# BatteryTestBoard_V1.net
KiCad netlist of a schematic drawn in EAGLE
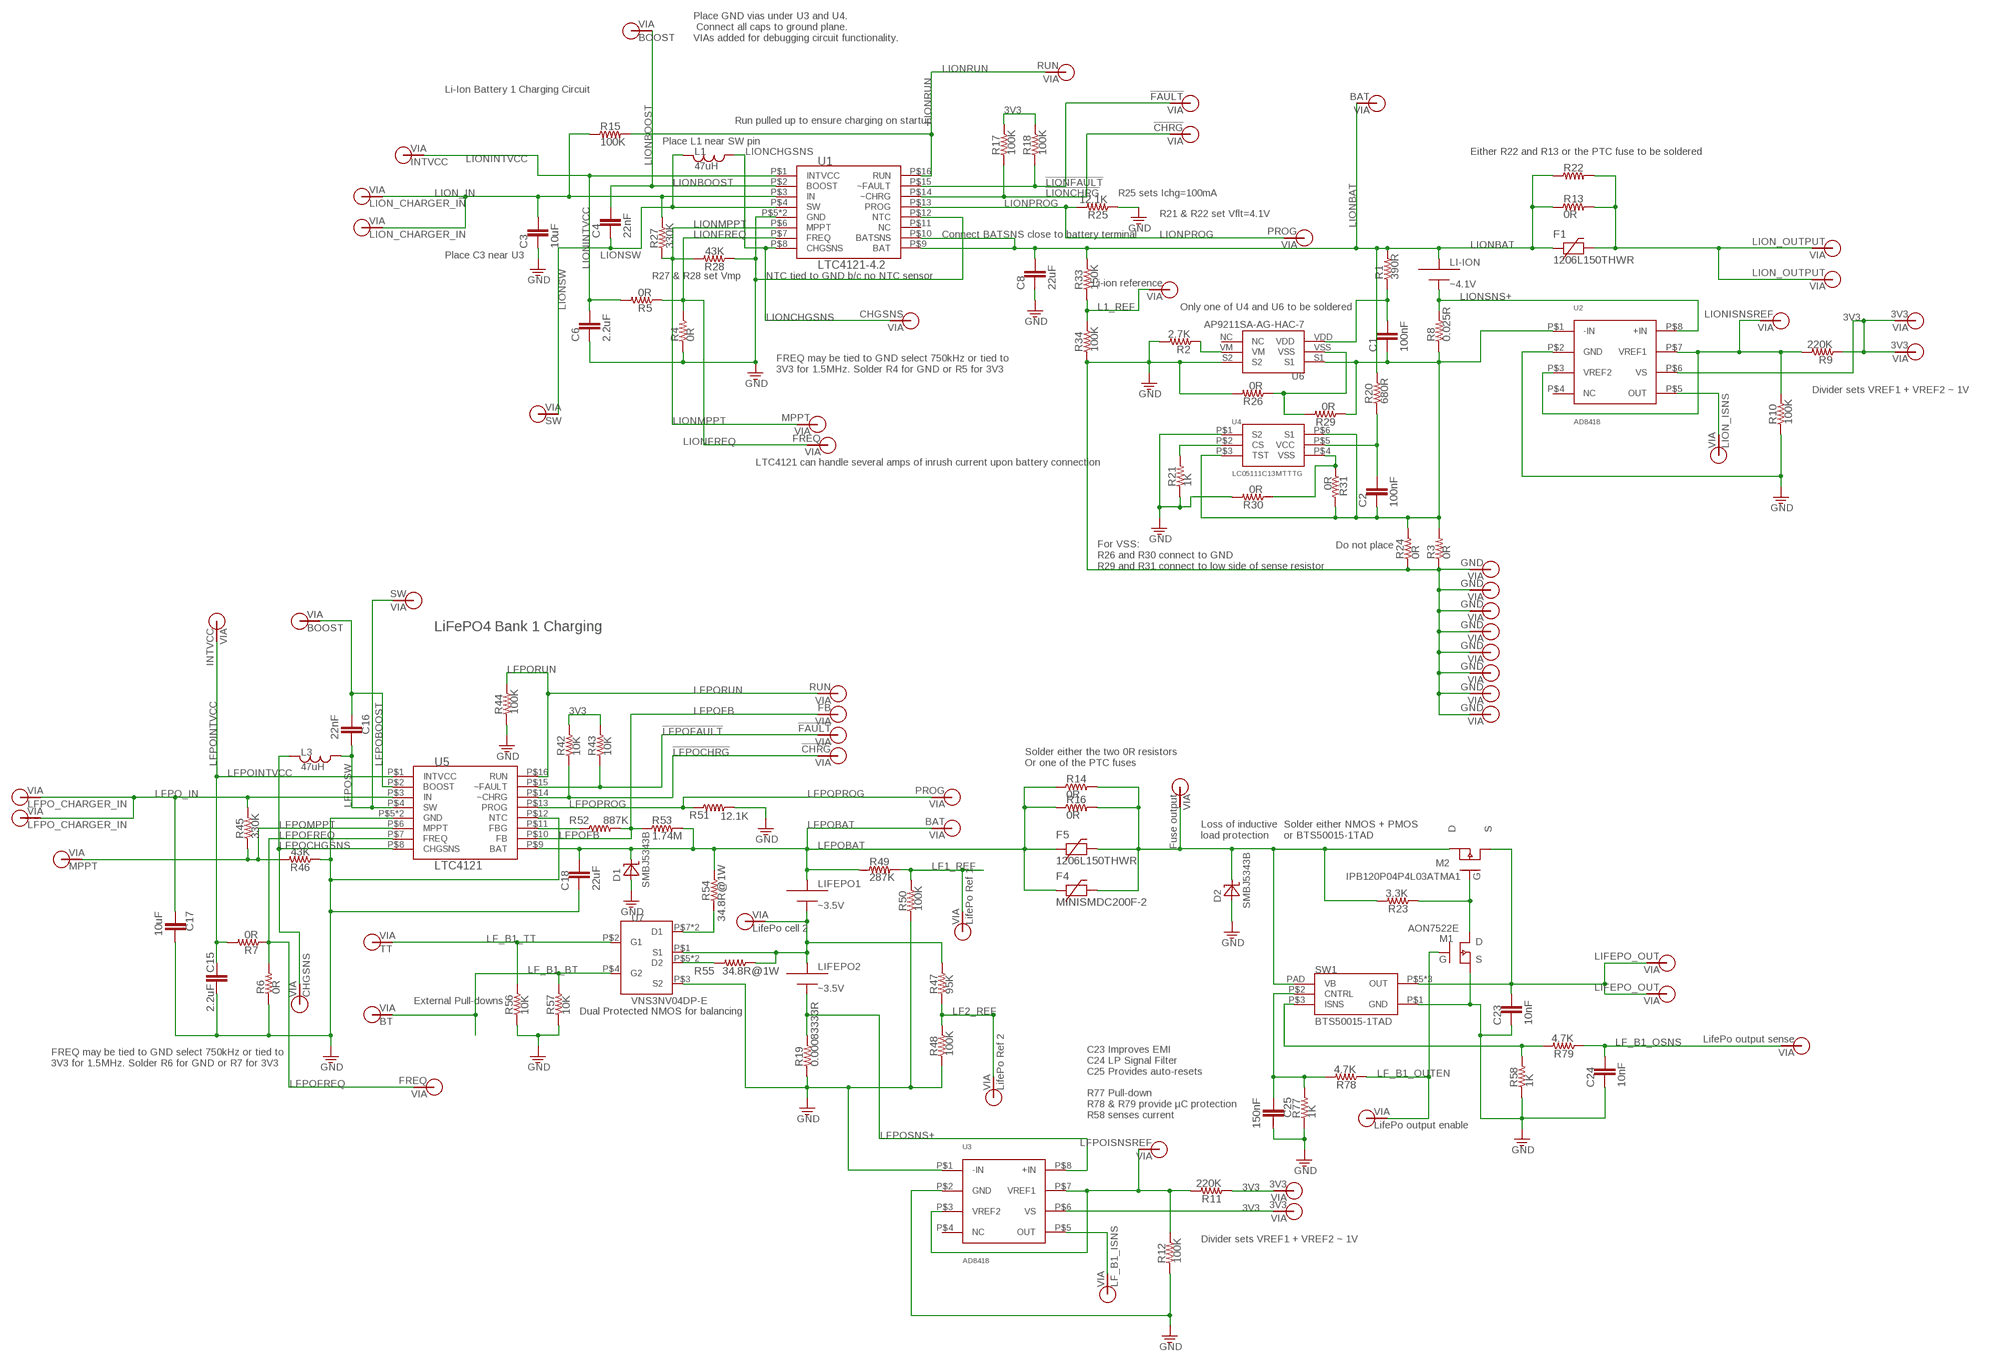
[diagram p0: schematic, sheet 1]

(export (version "E")
  (design (tool "Eeschema 10.0.6"))
  (components
    (comp (ref "C1")
      (value "100nF")
      (footprint "eagle-import:0805")
      (libsource (lib "eagle-import") (part "CAP0805"))
    )
    (comp (ref "C2")
      (value "100nF")
      (footprint "eagle-import:0805")
      (libsource (lib "eagle-import") (part "CAP0805"))
    )
    (comp (ref "C3")
      (value "10uF")
      (footprint "eagle-import:0805")
      (libsource (lib "eagle-import") (part "CAP0805"))
    )
    (comp (ref "C4")
      (value "22nF")
      (footprint "eagle-import:0805")
      (libsource (lib "eagle-import") (part "CAP0805"))
    )
    (comp (ref "C6")
      (value "2.2uF")
      (footprint "eagle-import:0805")
      (libsource (lib "eagle-import") (part "CAP0805"))
    )
    (comp (ref "C8")
      (value "22uF")
      (footprint "eagle-import:0805")
      (libsource (lib "eagle-import") (part "CAP0805"))
    )
    (comp (ref "C15")
      (value "2.2uF")
      (footprint "eagle-import:0805")
      (libsource (lib "eagle-import") (part "CAP0805"))
    )
    (comp (ref "C16")
      (value "22nF")
      (footprint "eagle-import:0805")
      (libsource (lib "eagle-import") (part "CAP0805"))
    )
    (comp (ref "C17")
      (value "10uF")
      (footprint "eagle-import:0805")
      (libsource (lib "eagle-import") (part "CAP0805"))
    )
    (comp (ref "C18")
      (value "22uF")
      (footprint "eagle-import:0805")
      (libsource (lib "eagle-import") (part "CAP0805"))
    )
    (comp (ref "C23")
      (value "10nF")
      (footprint "eagle-import:0805")
      (libsource (lib "eagle-import") (part "CAP0805"))
    )
    (comp (ref "C24")
      (value "10nF")
      (footprint "eagle-import:0805")
      (libsource (lib "eagle-import") (part "CAP0805"))
    )
    (comp (ref "C25")
      (value "150nF")
      (footprint "eagle-import:0805")
      (libsource (lib "eagle-import") (part "CAP0805"))
    )
    (comp (ref "D1")
      (value "SMBJ5343B")
      (footprint "eagle-import:DO214AA")
      (libsource (lib "eagle-import") (part "SMBJ5343B"))
    )
    (comp (ref "D2")
      (value "SMBJ5343B")
      (footprint "eagle-import:DO214AA")
      (libsource (lib "eagle-import") (part "SMBJ5343B"))
    )
    (comp (ref "F1")
      (value "1206L150THWR")
      (footprint "eagle-import:1206")
      (libsource (lib "eagle-import") (part "1206L150THWR"))
    )
    (comp (ref "F4")
      (value "MINISMDC200F-2")
      (footprint "eagle-import:1812")
      (libsource (lib "eagle-import") (part "MINISMDC200F-2"))
    )
    (comp (ref "F5")
      (value "1206L150THWR")
      (footprint "eagle-import:1206")
      (libsource (lib "eagle-import") (part "1206L150THWR"))
    )
    (comp (ref "L1")
      (value "47uH")
      (footprint "eagle-import:1812")
      (libsource (lib "eagle-import") (part "IND1812"))
    )
    (comp (ref "L3")
      (value "47uH")
      (footprint "eagle-import:1812")
      (libsource (lib "eagle-import") (part "IND1812"))
    )
    (comp (ref "LI-ION")
      (value "~4.1V")
      (footprint "eagle-import:EQUISAT-BATTERY-VA")
      (libsource (lib "eagle-import") (part "LI-ION"))
    )
    (comp (ref "LIFEPO1")
      (value "~3.5V")
      (footprint "eagle-import:EQUISAT-BATTERY-VA")
      (libsource (lib "eagle-import") (part "LIFEPO4VA"))
    )
    (comp (ref "LIFEPO2")
      (value "~3.5V")
      (footprint "eagle-import:EQUISAT-BATTERY-VA")
      (libsource (lib "eagle-import") (part "LIFEPO4VA"))
    )
    (comp (ref "M1")
      (value "AON7522E")
      (footprint "eagle-import:DFN-3X3-8")
      (libsource (lib "eagle-import") (part "AON7522E"))
    )
    (comp (ref "M2")
      (value "IPB120P04P4L03ATMA1")
      (footprint "eagle-import:TO263")
      (libsource (lib "eagle-import") (part "IPB120P04P4L03ATMA1"))
    )
    (comp (ref "R1")
      (value "390R")
      (footprint "eagle-import:0805")
      (libsource (lib "eagle-import") (part "RES0805"))
    )
    (comp (ref "R2")
      (value "2.7K")
      (footprint "eagle-import:0805")
      (libsource (lib "eagle-import") (part "RES0805"))
    )
    (comp (ref "R3")
      (value "0R")
      (footprint "eagle-import:1210")
      (libsource (lib "eagle-import") (part "RES1210"))
    )
    (comp (ref "R4")
      (value "0R")
      (footprint "eagle-import:0805")
      (libsource (lib "eagle-import") (part "RES0805"))
    )
    (comp (ref "R5")
      (value "0R")
      (footprint "eagle-import:0805")
      (libsource (lib "eagle-import") (part "RES0805"))
    )
    (comp (ref "R6")
      (value "0R")
      (footprint "eagle-import:0805")
      (libsource (lib "eagle-import") (part "RES0805"))
    )
    (comp (ref "R7")
      (value "0R")
      (footprint "eagle-import:0805")
      (libsource (lib "eagle-import") (part "RES0805"))
    )
    (comp (ref "R8")
      (value "0.025R")
      (footprint "eagle-import:1210")
      (libsource (lib "eagle-import") (part "RES1210"))
    )
    (comp (ref "R9")
      (value "220K")
      (footprint "eagle-import:0805")
      (libsource (lib "eagle-import") (part "RES0805"))
    )
    (comp (ref "R10")
      (value "100K")
      (footprint "eagle-import:0805")
      (libsource (lib "eagle-import") (part "RES0805"))
    )
    (comp (ref "R11")
      (value "220K")
      (footprint "eagle-import:0805")
      (libsource (lib "eagle-import") (part "RES0805"))
    )
    (comp (ref "R12")
      (value "100K")
      (footprint "eagle-import:0805")
      (libsource (lib "eagle-import") (part "RES0805"))
    )
    (comp (ref "R13")
      (value "0R")
      (footprint "eagle-import:1210")
      (libsource (lib "eagle-import") (part "RES1210"))
    )
    (comp (ref "R14")
      (value "0R")
      (footprint "eagle-import:1210")
      (libsource (lib "eagle-import") (part "RES1210"))
    )
    (comp (ref "R15")
      (value "100K")
      (footprint "eagle-import:0805")
      (libsource (lib "eagle-import") (part "RES0805"))
    )
    (comp (ref "R16")
      (value "0R")
      (footprint "eagle-import:1210")
      (libsource (lib "eagle-import") (part "RES1210"))
    )
    (comp (ref "R17")
      (value "100K")
      (footprint "eagle-import:0805")
      (libsource (lib "eagle-import") (part "RES0805"))
    )
    (comp (ref "R18")
      (value "100K")
      (footprint "eagle-import:0805")
      (libsource (lib "eagle-import") (part "RES0805"))
    )
    (comp (ref "R19")
      (value "0.00083333R")
      (footprint "eagle-import:1210")
      (libsource (lib "eagle-import") (part "RES1210"))
    )
    (comp (ref "R20")
      (value "680R")
      (footprint "eagle-import:0805")
      (libsource (lib "eagle-import") (part "RES0805"))
    )
    (comp (ref "R21")
      (value "1K")
      (footprint "eagle-import:0805")
      (libsource (lib "eagle-import") (part "RES0805"))
    )
    (comp (ref "R22")
      (value "0R")
      (footprint "eagle-import:1210")
      (libsource (lib "eagle-import") (part "RES1210"))
    )
    (comp (ref "R23")
      (value "3.3K")
      (footprint "eagle-import:0805")
      (libsource (lib "eagle-import") (part "RES0805"))
    )
    (comp (ref "R24")
      (value "0R")
      (footprint "eagle-import:1210")
      (libsource (lib "eagle-import") (part "RES1210"))
    )
    (comp (ref "R25")
      (value "12.1K")
      (footprint "eagle-import:0805")
      (libsource (lib "eagle-import") (part "RES0805"))
    )
    (comp (ref "R26")
      (value "0R")
      (footprint "eagle-import:0805")
      (libsource (lib "eagle-import") (part "RES0805"))
    )
    (comp (ref "R27")
      (value "330K")
      (footprint "eagle-import:0805")
      (libsource (lib "eagle-import") (part "RES0805"))
    )
    (comp (ref "R28")
      (value "43K")
      (footprint "eagle-import:0805")
      (libsource (lib "eagle-import") (part "RES0805"))
    )
    (comp (ref "R29")
      (value "0R")
      (footprint "eagle-import:0805")
      (libsource (lib "eagle-import") (part "RES0805"))
    )
    (comp (ref "R30")
      (value "0R")
      (footprint "eagle-import:0805")
      (libsource (lib "eagle-import") (part "RES0805"))
    )
    (comp (ref "R31")
      (value "0R")
      (footprint "eagle-import:0805")
      (libsource (lib "eagle-import") (part "RES0805"))
    )
    (comp (ref "R33")
      (value "150K")
      (footprint "eagle-import:0805")
      (libsource (lib "eagle-import") (part "RES0805"))
    )
    (comp (ref "R34")
      (value "100K")
      (footprint "eagle-import:0805")
      (libsource (lib "eagle-import") (part "RES0805"))
    )
    (comp (ref "R42")
      (value "10K")
      (footprint "eagle-import:0805")
      (libsource (lib "eagle-import") (part "RES0805"))
    )
    (comp (ref "R43")
      (value "10K")
      (footprint "eagle-import:0805")
      (libsource (lib "eagle-import") (part "RES0805"))
    )
    (comp (ref "R44")
      (value "100K")
      (footprint "eagle-import:0805")
      (libsource (lib "eagle-import") (part "RES0805"))
    )
    (comp (ref "R45")
      (value "330K")
      (footprint "eagle-import:0805")
      (libsource (lib "eagle-import") (part "RES0805"))
    )
    (comp (ref "R46")
      (value "43K")
      (footprint "eagle-import:0805")
      (libsource (lib "eagle-import") (part "RES0805"))
    )
    (comp (ref "R47")
      (value "95K")
      (footprint "eagle-import:0805")
      (libsource (lib "eagle-import") (part "RES0805"))
    )
    (comp (ref "R48")
      (value "100K")
      (footprint "eagle-import:0805")
      (libsource (lib "eagle-import") (part "RES0805"))
    )
    (comp (ref "R49")
      (value "287K")
      (footprint "eagle-import:0805")
      (libsource (lib "eagle-import") (part "RES0805"))
    )
    (comp (ref "R50")
      (value "100K")
      (footprint "eagle-import:0805")
      (libsource (lib "eagle-import") (part "RES0805"))
    )
    (comp (ref "R51")
      (value "12.1K")
      (footprint "eagle-import:0805")
      (libsource (lib "eagle-import") (part "RES0805"))
    )
    (comp (ref "R52")
      (value "887K")
      (footprint "eagle-import:0805")
      (libsource (lib "eagle-import") (part "RES0805"))
    )
    (comp (ref "R53")
      (value "1.74M")
      (footprint "eagle-import:0805")
      (libsource (lib "eagle-import") (part "RES0805"))
    )
    (comp (ref "R54")
      (value "34.8R@1W")
      (footprint "eagle-import:1210")
      (libsource (lib "eagle-import") (part "RES1210"))
    )
    (comp (ref "R55")
      (value "34.8R@1W")
      (footprint "eagle-import:1210")
      (libsource (lib "eagle-import") (part "RES1210"))
    )
    (comp (ref "R56")
      (value "10K")
      (footprint "eagle-import:0805")
      (libsource (lib "eagle-import") (part "RES0805"))
    )
    (comp (ref "R57")
      (value "10K")
      (footprint "eagle-import:0805")
      (libsource (lib "eagle-import") (part "RES0805"))
    )
    (comp (ref "R58")
      (value "1K")
      (footprint "eagle-import:0805")
      (libsource (lib "eagle-import") (part "RES0805"))
    )
    (comp (ref "R77")
      (value "1K")
      (footprint "eagle-import:0805")
      (libsource (lib "eagle-import") (part "RES0805"))
    )
    (comp (ref "R78")
      (value "4.7K")
      (footprint "eagle-import:0805")
      (libsource (lib "eagle-import") (part "RES0805"))
    )
    (comp (ref "R79")
      (value "4.7K")
      (footprint "eagle-import:0805")
      (libsource (lib "eagle-import") (part "RES0805"))
    )
    (comp (ref "SW1")
      (value "BTS50015-1TAD")
      (footprint "eagle-import:TO-263-7-8")
      (libsource (lib "eagle-import") (part "BTS50015-1TAD"))
    )
    (comp (ref "U1")
      (value "LTC4121-4.2")
      (footprint "eagle-import:QFN-16-PAD")
      (libsource (lib "eagle-import") (part "LTC4121-4.2"))
    )
    (comp (ref "U2")
      (value "AD8418")
      (footprint "eagle-import:MSOP-8")
      (libsource (lib "eagle-import") (part "AD8418"))
    )
    (comp (ref "U3")
      (value "AD8418")
      (footprint "eagle-import:MSOP-8")
      (libsource (lib "eagle-import") (part "AD8418"))
    )
    (comp (ref "U4")
      (value "LC05111C13MTTTG")
      (footprint "eagle-import:WDFN6")
      (libsource (lib "eagle-import") (part "LC05111C13MTTTG"))
    )
    (comp (ref "U5")
      (value "LTC4121")
      (footprint "eagle-import:QFN-16-PAD")
      (libsource (lib "eagle-import") (part "LTC4121"))
    )
    (comp (ref "U6")
      (value "AP9211SA-AG-HAC-7")
      (footprint "eagle-import:U-DFN2030-6")
      (libsource (lib "eagle-import") (part "AP9211SA-AG-HAC-7"))
    )
    (comp (ref "U7")
      (value "VNS3NV04DP-E")
      (footprint "eagle-import:SO-8")
      (libsource (lib "eagle-import") (part "VNS3NV04DP-E"))
    )
    (comp (ref "V1")
      (value "LION_OUTPUT")
      (footprint "eagle-import:VIA-120MIL")
      (libsource (lib "eagle-import") (part "VIA-120MIL"))
    )
    (comp (ref "V2")
      (value "Fuse output")
      (footprint "eagle-import:VIA-60MIL-SQ")
      (libsource (lib "eagle-import") (part "VIA60MIL-SQ"))
    )
    (comp (ref "V3")
      (value "GND")
      (footprint "eagle-import:VIA-60MIL-SQ")
      (libsource (lib "eagle-import") (part "VIA60MIL-SQ"))
    )
    (comp (ref "V4")
      (value "GND")
      (footprint "eagle-import:VIA-60MIL-SQ")
      (libsource (lib "eagle-import") (part "VIA60MIL-SQ"))
    )
    (comp (ref "V5")
      (value "GND")
      (footprint "eagle-import:VIA-60MIL-SQ")
      (libsource (lib "eagle-import") (part "VIA60MIL-SQ"))
    )
    (comp (ref "V6")
      (value "GND")
      (footprint "eagle-import:VIA-60MIL-SQ")
      (libsource (lib "eagle-import") (part "VIA60MIL-SQ"))
    )
    (comp (ref "V7")
      (value "GND")
      (footprint "eagle-import:VIA-60MIL-SQ")
      (libsource (lib "eagle-import") (part "VIA60MIL-SQ"))
    )
    (comp (ref "V8")
      (value "GND")
      (footprint "eagle-import:VIA-60MIL-SQ")
      (libsource (lib "eagle-import") (part "VIA60MIL-SQ"))
    )
    (comp (ref "V9")
      (value "LFPO_CHARGER_IN")
      (footprint "eagle-import:VIA-60MIL-SQ")
      (libsource (lib "eagle-import") (part "VIA60MIL-SQ"))
    )
    (comp (ref "V10")
      (value "GND")
      (footprint "eagle-import:VIA-60MIL-SQ")
      (libsource (lib "eagle-import") (part "VIA60MIL-SQ"))
    )
    (comp (ref "V11")
      (value "LFPOISNSREF")
      (footprint "eagle-import:VIA-60MIL-SQ")
      (libsource (lib "eagle-import") (part "VIA60MIL-SQ"))
    )
    (comp (ref "V12")
      (value "LIONISNSREF")
      (footprint "eagle-import:VIA-60MIL-SQ")
      (libsource (lib "eagle-import") (part "VIA60MIL-SQ"))
    )
    (comp (ref "V13")
      (value "LF_B1_ISNS")
      (footprint "eagle-import:VIA-60MIL-SQ")
      (libsource (lib "eagle-import") (part "VIA60MIL-SQ"))
    )
    (comp (ref "V16")
      (value "LifePo cell 2")
      (footprint "eagle-import:VIA-60MIL-SQ")
      (libsource (lib "eagle-import") (part "VIA60MIL-SQ"))
    )
    (comp (ref "V20")
      (value "LifePo output enable")
      (footprint "eagle-import:VIA-60MIL-SQ")
      (libsource (lib "eagle-import") (part "VIA60MIL-SQ"))
    )
    (comp (ref "V21")
      (value "LIFEPO_OUT")
      (footprint "eagle-import:VIA-120MIL")
      (libsource (lib "eagle-import") (part "VIA-120MIL"))
    )
    (comp (ref "V26")
      (value "LIFEPO_OUT")
      (footprint "eagle-import:VIA-120MIL")
      (libsource (lib "eagle-import") (part "VIA-120MIL"))
    )
    (comp (ref "V29")
      (value "TT")
      (footprint "eagle-import:VIA-60MIL-SQ")
      (libsource (lib "eagle-import") (part "VIA60MIL-SQ"))
    )
    (comp (ref "V31")
      (value "LifePo output sense")
      (footprint "eagle-import:VIA-60MIL-SQ")
      (libsource (lib "eagle-import") (part "VIA60MIL-SQ"))
    )
    (comp (ref "V32")
      (value "BT")
      (footprint "eagle-import:VIA-60MIL-SQ")
      (libsource (lib "eagle-import") (part "VIA60MIL-SQ"))
    )
    (comp (ref "V34")
      (value "LION_CHARGER_IN")
      (footprint "eagle-import:VIA-60MIL-SQ")
      (libsource (lib "eagle-import") (part "VIA60MIL-SQ"))
    )
    (comp (ref "V35")
      (value "LION_CHARGER_IN")
      (footprint "eagle-import:VIA-60MIL-SQ")
      (libsource (lib "eagle-import") (part "VIA60MIL-SQ"))
    )
    (comp (ref "V36")
      (value "BOOST")
      (footprint "eagle-import:VIA-60MIL-SQ")
      (libsource (lib "eagle-import") (part "VIA60MIL-SQ"))
    )
    (comp (ref "V37")
      (value "LION_OUTPUT")
      (footprint "eagle-import:VIA-120MIL")
      (libsource (lib "eagle-import") (part "VIA-120MIL"))
    )
    (comp (ref "V38")
      (value "SW")
      (footprint "eagle-import:VIA-60MIL-SQ")
      (libsource (lib "eagle-import") (part "VIA60MIL-SQ"))
    )
    (comp (ref "V39")
      (value "MPPT")
      (footprint "eagle-import:VIA-60MIL-SQ")
      (libsource (lib "eagle-import") (part "VIA60MIL-SQ"))
    )
    (comp (ref "V41")
      (value "GND")
      (footprint "eagle-import:VIA-60MIL-SQ")
      (libsource (lib "eagle-import") (part "VIA60MIL-SQ"))
    )
    (comp (ref "V43")
      (value "LION_ISNS")
      (footprint "eagle-import:VIA-60MIL-SQ")
      (libsource (lib "eagle-import") (part "VIA60MIL-SQ"))
    )
    (comp (ref "V44")
      (value "Li-ion reference")
      (footprint "eagle-import:VIA-60MIL-SQ")
      (libsource (lib "eagle-import") (part "VIA60MIL-SQ"))
    )
    (comp (ref "V46")
      (value "CHGSNS")
      (footprint "eagle-import:VIA-60MIL-SQ")
      (libsource (lib "eagle-import") (part "VIA60MIL-SQ"))
    )
    (comp (ref "V47")
      (value "FREQ")
      (footprint "eagle-import:VIA-60MIL-SQ")
      (libsource (lib "eagle-import") (part "VIA60MIL-SQ"))
    )
    (comp (ref "V48")
      (value "BAT")
      (footprint "eagle-import:VIA-60MIL-SQ")
      (libsource (lib "eagle-import") (part "VIA60MIL-SQ"))
    )
    (comp (ref "V50")
      (value "PROG")
      (footprint "eagle-import:VIA-60MIL-SQ")
      (libsource (lib "eagle-import") (part "VIA60MIL-SQ"))
    )
    (comp (ref "V51")
      (value "!CHRG")
      (footprint "eagle-import:VIA-60MIL-SQ")
      (libsource (lib "eagle-import") (part "VIA60MIL-SQ"))
    )
    (comp (ref "V52")
      (value "!FAULT")
      (footprint "eagle-import:VIA-60MIL-SQ")
      (libsource (lib "eagle-import") (part "VIA60MIL-SQ"))
    )
    (comp (ref "V53")
      (value "RUN")
      (footprint "eagle-import:VIA-60MIL-SQ")
      (libsource (lib "eagle-import") (part "VIA60MIL-SQ"))
    )
    (comp (ref "V54")
      (value "BOOST")
      (footprint "eagle-import:VIA-60MIL-SQ")
      (libsource (lib "eagle-import") (part "VIA60MIL-SQ"))
    )
    (comp (ref "V55")
      (value "INTVCC")
      (footprint "eagle-import:VIA-60MIL-SQ")
      (libsource (lib "eagle-import") (part "VIA60MIL-SQ"))
    )
    (comp (ref "V57")
      (value "SW")
      (footprint "eagle-import:VIA-60MIL-SQ")
      (libsource (lib "eagle-import") (part "VIA60MIL-SQ"))
    )
    (comp (ref "V58")
      (value "LifePo Ref 1")
      (footprint "eagle-import:VIA-60MIL-SQ")
      (libsource (lib "eagle-import") (part "VIA60MIL-SQ"))
    )
    (comp (ref "V59")
      (value "LifePo Ref 2")
      (footprint "eagle-import:VIA-60MIL-SQ")
      (libsource (lib "eagle-import") (part "VIA60MIL-SQ"))
    )
    (comp (ref "V60")
      (value "MPPT")
      (footprint "eagle-import:VIA-60MIL-SQ")
      (libsource (lib "eagle-import") (part "VIA60MIL-SQ"))
    )
    (comp (ref "V61")
      (value "CHGSNS")
      (footprint "eagle-import:VIA-60MIL-SQ")
      (libsource (lib "eagle-import") (part "VIA60MIL-SQ"))
    )
    (comp (ref "V62")
      (value "FREQ")
      (footprint "eagle-import:VIA-60MIL-SQ")
      (libsource (lib "eagle-import") (part "VIA60MIL-SQ"))
    )
    (comp (ref "V63")
      (value "BAT")
      (footprint "eagle-import:VIA-60MIL-SQ")
      (libsource (lib "eagle-import") (part "VIA60MIL-SQ"))
    )
    (comp (ref "V65")
      (value "PROG")
      (footprint "eagle-import:VIA-60MIL-SQ")
      (libsource (lib "eagle-import") (part "VIA60MIL-SQ"))
    )
    (comp (ref "V66")
      (value "!CHRG")
      (footprint "eagle-import:VIA-60MIL-SQ")
      (libsource (lib "eagle-import") (part "VIA60MIL-SQ"))
    )
    (comp (ref "V67")
      (value "!FAULT")
      (footprint "eagle-import:VIA-60MIL-SQ")
      (libsource (lib "eagle-import") (part "VIA60MIL-SQ"))
    )
    (comp (ref "V68")
      (value "RUN")
      (footprint "eagle-import:VIA-60MIL-SQ")
      (libsource (lib "eagle-import") (part "VIA60MIL-SQ"))
    )
    (comp (ref "V69")
      (value "INTVCC")
      (footprint "eagle-import:VIA-60MIL-SQ")
      (libsource (lib "eagle-import") (part "VIA60MIL-SQ"))
    )
    (comp (ref "V70")
      (value "FB")
      (footprint "eagle-import:VIA-60MIL-SQ")
      (libsource (lib "eagle-import") (part "VIA60MIL-SQ"))
    )
    (comp (ref "V71")
      (value "3V3")
      (footprint "eagle-import:VIA-60MIL-SQ")
      (libsource (lib "eagle-import") (part "VIA60MIL-SQ"))
    )
    (comp (ref "V72")
      (value "3V3")
      (footprint "eagle-import:VIA-60MIL-SQ")
      (libsource (lib "eagle-import") (part "VIA60MIL-SQ"))
    )
    (comp (ref "V73")
      (value "3V3")
      (footprint "eagle-import:VIA-60MIL-SQ")
      (libsource (lib "eagle-import") (part "VIA60MIL-SQ"))
    )
    (comp (ref "V74")
      (value "3V3")
      (footprint "eagle-import:VIA-60MIL-SQ")
      (libsource (lib "eagle-import") (part "VIA60MIL-SQ"))
    )
    (comp (ref "V75")
      (value "LFPO_CHARGER_IN")
      (footprint "eagle-import:VIA-60MIL-SQ")
      (libsource (lib "eagle-import") (part "VIA60MIL-SQ"))
    )
  )
  (nets
    (net (code "1") (name "/3V3") (class "Default")
      (node (ref "R11") (pin "1") (pinfunction "1_1") (pintype "passive"))
      (node (ref "R17") (pin "2") (pinfunction "2_2") (pintype "passive"))
      (node (ref "R18") (pin "2") (pinfunction "2_2") (pintype "passive"))
      (node (ref "R42") (pin "2") (pinfunction "2_2") (pintype "passive"))
      (node (ref "R43") (pin "2") (pinfunction "2_2") (pintype "passive"))
      (node (ref "R9") (pin "1") (pinfunction "1_1") (pintype "passive"))
      (node (ref "U2") (pin "P$6") (pinfunction "VS_P$6") (pintype "bidirectional"))
      (node (ref "U3") (pin "P$6") (pinfunction "VS_P$6") (pintype "bidirectional"))
      (node (ref "V71") (pin "P$1") (pinfunction "P$1_P$1") (pintype "bidirectional"))
      (node (ref "V72") (pin "P$1") (pinfunction "P$1_P$1") (pintype "bidirectional"))
      (node (ref "V73") (pin "P$1") (pinfunction "P$1_P$1") (pintype "bidirectional"))
      (node (ref "V74") (pin "P$1") (pinfunction "P$1_P$1") (pintype "bidirectional"))
    )
    (net (code "2") (name "/L1_REF") (class "Default")
      (node (ref "R33") (pin "1") (pinfunction "1_1") (pintype "passive"))
      (node (ref "R34") (pin "2") (pinfunction "2_2") (pintype "passive"))
      (node (ref "V44") (pin "P$1") (pinfunction "P$1_P$1") (pintype "bidirectional"))
    )
    (net (code "3") (name "/LF1_REF") (class "Default")
      (node (ref "R49") (pin "2") (pinfunction "2_2") (pintype "passive"))
      (node (ref "R50") (pin "2") (pinfunction "2_2") (pintype "passive"))
      (node (ref "V58") (pin "P$1") (pinfunction "P$1_P$1") (pintype "bidirectional"))
    )
    (net (code "4") (name "/LF2_REF") (class "Default")
      (node (ref "R47") (pin "1") (pinfunction "1_1") (pintype "passive"))
      (node (ref "R48") (pin "2") (pinfunction "2_2") (pintype "passive"))
      (node (ref "V59") (pin "P$1") (pinfunction "P$1_P$1") (pintype "bidirectional"))
    )
    (net (code "5") (name "/LFPOBAT") (class "Default")
      (node (ref "C18") (pin "1") (pinfunction "P$1_1") (pintype "passive"))
      (node (ref "D1") (pin "C") (pinfunction "C_C") (pintype "passive"))
      (node (ref "F4") (pin "P$1") (pinfunction "P$1_P$1") (pintype "passive"))
      (node (ref "F5") (pin "1") (pinfunction "P$1_1") (pintype "passive"))
      (node (ref "LIFEPO1") (pin "PLUS") (pinfunction "PLUS_PLUS") (pintype "power_in"))
      (node (ref "R14") (pin "P$1") (pinfunction "1_P$1") (pintype "passive"))
      (node (ref "R16") (pin "P$1") (pinfunction "1_P$1") (pintype "passive"))
      (node (ref "R49") (pin "1") (pinfunction "1_1") (pintype "passive"))
      (node (ref "R53") (pin "2") (pinfunction "2_2") (pintype "passive"))
      (node (ref "R54") (pin "P$2") (pinfunction "2_P$2") (pintype "passive"))
      (node (ref "U5") (pin "P$9") (pinfunction "BAT_P$9") (pintype "bidirectional"))
      (node (ref "V63") (pin "P$1") (pinfunction "P$1_P$1") (pintype "bidirectional"))
    )
    (net (code "6") (name "/LFPOBOOST") (class "Default")
      (node (ref "C16") (pin "2") (pinfunction "P$2_2") (pintype "passive"))
      (node (ref "U5") (pin "P$2") (pinfunction "BOOST_P$2") (pintype "bidirectional"))
      (node (ref "V54") (pin "P$1") (pinfunction "P$1_P$1") (pintype "bidirectional"))
    )
    (net (code "7") (name "/LFPOCHGSNS") (class "Default")
      (node (ref "L3") (pin "P$1") (pinfunction "P$1_P$1") (pintype "passive"))
      (node (ref "U5") (pin "P$8") (pinfunction "CHGSNS_P$8") (pintype "bidirectional"))
      (node (ref "V61") (pin "P$1") (pinfunction "P$1_P$1") (pintype "bidirectional"))
    )
    (net (code "8") (name "/LFPOFB") (class "Default")
      (node (ref "R52") (pin "2") (pinfunction "2_2") (pintype "passive"))
      (node (ref "R53") (pin "1") (pinfunction "1_1") (pintype "passive"))
      (node (ref "U5") (pin "P$10") (pinfunction "FB_P$10") (pintype "bidirectional"))
      (node (ref "V70") (pin "P$1") (pinfunction "P$1_P$1") (pintype "bidirectional"))
    )
    (net (code "9") (name "/LFPOFREQ") (class "Default")
      (node (ref "R6") (pin "2") (pinfunction "2_2") (pintype "passive"))
      (node (ref "R7") (pin "1") (pinfunction "1_1") (pintype "passive"))
      (node (ref "U5") (pin "P$7") (pinfunction "FREQ_P$7") (pintype "bidirectional"))
      (node (ref "V62") (pin "P$1") (pinfunction "P$1_P$1") (pintype "bidirectional"))
    )
    (net (code "10") (name "/LFPOINTVCC") (class "Default")
      (node (ref "C15") (pin "2") (pinfunction "P$2_2") (pintype "passive"))
      (node (ref "R7") (pin "2") (pinfunction "2_2") (pintype "passive"))
      (node (ref "U5") (pin "P$1") (pinfunction "INTVCC_P$1") (pintype "bidirectional"))
      (node (ref "V69") (pin "P$1") (pinfunction "P$1_P$1") (pintype "bidirectional"))
    )
    (net (code "11") (name "/LFPOMPPT") (class "Default")
      (node (ref "R45") (pin "1") (pinfunction "1_1") (pintype "passive"))
      (node (ref "R46") (pin "2") (pinfunction "2_2") (pintype "passive"))
      (node (ref "U5") (pin "P$6") (pinfunction "MPPT_P$6") (pintype "bidirectional"))
      (node (ref "V60") (pin "P$1") (pinfunction "P$1_P$1") (pintype "bidirectional"))
    )
    (net (code "12") (name "/LFPOPROG") (class "Default")
      (node (ref "R51") (pin "1") (pinfunction "1_1") (pintype "passive"))
      (node (ref "U5") (pin "P$13") (pinfunction "PROG_P$13") (pintype "bidirectional"))
      (node (ref "V65") (pin "P$1") (pinfunction "P$1_P$1") (pintype "bidirectional"))
    )
    (net (code "13") (name "/LFPORUN") (class "Default")
      (node (ref "R44") (pin "2") (pinfunction "2_2") (pintype "passive"))
      (node (ref "U5") (pin "P$16") (pinfunction "RUN_P$16") (pintype "bidirectional"))
      (node (ref "V68") (pin "P$1") (pinfunction "P$1_P$1") (pintype "bidirectional"))
    )
    (net (code "14") (name "/LFPOSNS+") (class "Default")
      (node (ref "LIFEPO2") (pin "MINUS") (pinfunction "MINUS_MINUS") (pintype "power_in"))
      (node (ref "R19") (pin "P$2") (pinfunction "2_P$2") (pintype "passive"))
      (node (ref "U3") (pin "P$8") (pinfunction "+IN_P$8") (pintype "bidirectional"))
    )
    (net (code "15") (name "/LFPOSW") (class "Default")
      (node (ref "C16") (pin "1") (pinfunction "P$1_1") (pintype "passive"))
      (node (ref "L3") (pin "P$2") (pinfunction "P$2_P$2") (pintype "passive"))
      (node (ref "U5") (pin "P$4") (pinfunction "SW_P$4") (pintype "bidirectional"))
      (node (ref "V57") (pin "P$1") (pinfunction "P$1_P$1") (pintype "bidirectional"))
    )
    (net (code "16") (name "/LFPO_IN") (class "Default")
      (node (ref "C17") (pin "2") (pinfunction "P$2_2") (pintype "passive"))
      (node (ref "R45") (pin "2") (pinfunction "2_2") (pintype "passive"))
      (node (ref "U5") (pin "P$3") (pinfunction "IN_P$3") (pintype "bidirectional"))
      (node (ref "V75") (pin "P$1") (pinfunction "P$1_P$1") (pintype "bidirectional"))
      (node (ref "V9") (pin "P$1") (pinfunction "P$1_P$1") (pintype "bidirectional"))
    )
    (net (code "17") (name "/LF_B1_BT") (class "Default")
      (node (ref "R57") (pin "2") (pinfunction "2_2") (pintype "passive"))
      (node (ref "U7") (pin "P$4") (pinfunction "G2_P$4") (pintype "bidirectional"))
      (node (ref "V32") (pin "P$1") (pinfunction "P$1_P$1") (pintype "bidirectional"))
    )
    (net (code "18") (name "/LF_B1_OSNS") (class "Default")
      (node (ref "C24") (pin "1") (pinfunction "P$1_1") (pintype "passive"))
      (node (ref "R79") (pin "1") (pinfunction "1_1") (pintype "passive"))
      (node (ref "V31") (pin "P$1") (pinfunction "P$1_P$1") (pintype "bidirectional"))
    )
    (net (code "19") (name "/LF_B1_OUTEN") (class "Default")
      (node (ref "M1") (pin "P$4") (pinfunction "G_P$4") (pintype "bidirectional"))
      (node (ref "R78") (pin "1") (pinfunction "1_1") (pintype "passive"))
      (node (ref "V20") (pin "P$1") (pinfunction "P$1_P$1") (pintype "bidirectional"))
    )
    (net (code "20") (name "/LF_B1_TT") (class "Default")
      (node (ref "R56") (pin "2") (pinfunction "2_2") (pintype "passive"))
      (node (ref "U7") (pin "P$2") (pinfunction "G1_P$2") (pintype "bidirectional"))
      (node (ref "V29") (pin "P$1") (pinfunction "P$1_P$1") (pintype "bidirectional"))
    )
    (net (code "21") (name "/LIONBAT") (class "Default")
      (node (ref "C8") (pin "1") (pinfunction "P$1_1") (pintype "passive"))
      (node (ref "F1") (pin "1") (pinfunction "P$1_1") (pintype "passive"))
      (node (ref "LI-ION") (pin "PLUS") (pinfunction "PLUS_PLUS") (pintype "power_in"))
      (node (ref "R1") (pin "2") (pinfunction "2_2") (pintype "passive"))
      (node (ref "R13") (pin "P$1") (pinfunction "1_P$1") (pintype "passive"))
      (node (ref "R20") (pin "2") (pinfunction "2_2") (pintype "passive"))
      (node (ref "R22") (pin "P$1") (pinfunction "1_P$1") (pintype "passive"))
      (node (ref "R33") (pin "2") (pinfunction "2_2") (pintype "passive"))
      (node (ref "U1") (pin "P$10") (pinfunction "BATSNS_P$10") (pintype "bidirectional"))
      (node (ref "U1") (pin "P$9") (pinfunction "BAT_P$9") (pintype "bidirectional"))
      (node (ref "V48") (pin "P$1") (pinfunction "P$1_P$1") (pintype "bidirectional"))
    )
    (net (code "22") (name "/LIONBOOST") (class "Default")
      (node (ref "C4") (pin "1") (pinfunction "P$1_1") (pintype "passive"))
      (node (ref "U1") (pin "P$2") (pinfunction "BOOST_P$2") (pintype "bidirectional"))
      (node (ref "V36") (pin "P$1") (pinfunction "P$1_P$1") (pintype "bidirectional"))
    )
    (net (code "23") (name "/LIONCHGSNS") (class "Default")
      (node (ref "L1") (pin "P$2") (pinfunction "P$2_P$2") (pintype "passive"))
      (node (ref "U1") (pin "P$8") (pinfunction "CHGSNS_P$8") (pintype "bidirectional"))
      (node (ref "V46") (pin "P$1") (pinfunction "P$1_P$1") (pintype "bidirectional"))
    )
    (net (code "24") (name "/LIONFREQ") (class "Default")
      (node (ref "R4") (pin "2") (pinfunction "2_2") (pintype "passive"))
      (node (ref "R5") (pin "1") (pinfunction "1_1") (pintype "passive"))
      (node (ref "U1") (pin "P$7") (pinfunction "FREQ_P$7") (pintype "bidirectional"))
      (node (ref "V47") (pin "P$1") (pinfunction "P$1_P$1") (pintype "bidirectional"))
    )
    (net (code "25") (name "/LIONINTVCC") (class "Default")
      (node (ref "C6") (pin "1") (pinfunction "P$1_1") (pintype "passive"))
      (node (ref "R5") (pin "2") (pinfunction "2_2") (pintype "passive"))
      (node (ref "U1") (pin "P$1") (pinfunction "INTVCC_P$1") (pintype "bidirectional"))
      (node (ref "V55") (pin "P$1") (pinfunction "P$1_P$1") (pintype "bidirectional"))
    )
    (net (code "26") (name "/LIONMPPT") (class "Default")
      (node (ref "R27") (pin "1") (pinfunction "1_1") (pintype "passive"))
      (node (ref "R28") (pin "2") (pinfunction "2_2") (pintype "passive"))
      (node (ref "U1") (pin "P$6") (pinfunction "MPPT_P$6") (pintype "bidirectional"))
      (node (ref "V39") (pin "P$1") (pinfunction "P$1_P$1") (pintype "bidirectional"))
    )
    (net (code "27") (name "/LIONPROG") (class "Default")
      (node (ref "R25") (pin "2") (pinfunction "2_2") (pintype "passive"))
      (node (ref "U1") (pin "P$13") (pinfunction "PROG_P$13") (pintype "bidirectional"))
      (node (ref "V50") (pin "P$1") (pinfunction "P$1_P$1") (pintype "bidirectional"))
    )
    (net (code "28") (name "/LIONRUN") (class "Default")
      (node (ref "R15") (pin "2") (pinfunction "2_2") (pintype "passive"))
      (node (ref "U1") (pin "P$16") (pinfunction "RUN_P$16") (pintype "bidirectional"))
      (node (ref "V53") (pin "P$1") (pinfunction "P$1_P$1") (pintype "bidirectional"))
    )
    (net (code "29") (name "/LIONSNS+") (class "Default")
      (node (ref "LI-ION") (pin "MINUS") (pinfunction "MINUS_MINUS") (pintype "power_in"))
      (node (ref "R8") (pin "P$2") (pinfunction "2_P$2") (pintype "passive"))
      (node (ref "U2") (pin "P$8") (pinfunction "+IN_P$8") (pintype "bidirectional"))
    )
    (net (code "30") (name "/LIONSW") (class "Default")
      (node (ref "C4") (pin "2") (pinfunction "P$2_2") (pintype "passive"))
      (node (ref "L1") (pin "P$1") (pinfunction "P$1_P$1") (pintype "passive"))
      (node (ref "U1") (pin "P$4") (pinfunction "SW_P$4") (pintype "bidirectional"))
      (node (ref "V38") (pin "P$1") (pinfunction "P$1_P$1") (pintype "bidirectional"))
    )
    (net (code "31") (name "/LION_IN") (class "Default")
      (node (ref "C3") (pin "1") (pinfunction "P$1_1") (pintype "passive"))
      (node (ref "R15") (pin "1") (pinfunction "1_1") (pintype "passive"))
      (node (ref "R27") (pin "2") (pinfunction "2_2") (pintype "passive"))
      (node (ref "U1") (pin "P$3") (pinfunction "IN_P$3") (pintype "bidirectional"))
      (node (ref "V34") (pin "P$1") (pinfunction "P$1_P$1") (pintype "bidirectional"))
      (node (ref "V35") (pin "P$1") (pinfunction "P$1_P$1") (pintype "bidirectional"))
    )
    (net (code "32") (name "/~{LFPOCHRG}") (class "Default")
      (node (ref "R42") (pin "1") (pinfunction "1_1") (pintype "passive"))
      (node (ref "U5") (pin "P$14") (pinfunction "~{CHRG}_P$14") (pintype "bidirectional"))
      (node (ref "V66") (pin "P$1") (pinfunction "P$1_P$1") (pintype "bidirectional"))
    )
    (net (code "33") (name "/~{LFPOFAULT}") (class "Default")
      (node (ref "R43") (pin "1") (pinfunction "1_1") (pintype "passive"))
      (node (ref "U5") (pin "P$15") (pinfunction "~{FAULT}_P$15") (pintype "bidirectional"))
      (node (ref "V67") (pin "P$1") (pinfunction "P$1_P$1") (pintype "bidirectional"))
    )
    (net (code "34") (name "/~{LIONCHRG}") (class "Default")
      (node (ref "R17") (pin "1") (pinfunction "1_1") (pintype "passive"))
      (node (ref "U1") (pin "P$14") (pinfunction "~{CHRG}_P$14") (pintype "bidirectional"))
      (node (ref "V51") (pin "P$1") (pinfunction "P$1_P$1") (pintype "bidirectional"))
    )
    (net (code "35") (name "/~{LIONFAULT}") (class "Default")
      (node (ref "R18") (pin "1") (pinfunction "1_1") (pintype "passive"))
      (node (ref "U1") (pin "P$15") (pinfunction "~{FAULT}_P$15") (pintype "bidirectional"))
      (node (ref "V52") (pin "P$1") (pinfunction "P$1_P$1") (pintype "bidirectional"))
    )
    (net (code "36") (name "GND") (class "Default")
      (node (ref "C15") (pin "1") (pinfunction "P$1_1") (pintype "passive"))
      (node (ref "C17") (pin "1") (pinfunction "P$1_1") (pintype "passive"))
      (node (ref "C18") (pin "2") (pinfunction "P$2_2") (pintype "passive"))
      (node (ref "C23") (pin "2") (pinfunction "P$2_2") (pintype "passive"))
      (node (ref "C24") (pin "2") (pinfunction "P$2_2") (pintype "passive"))
      (node (ref "C25") (pin "1") (pinfunction "P$1_1") (pintype "passive"))
      (node (ref "C3") (pin "2") (pinfunction "P$2_2") (pintype "passive"))
      (node (ref "C6") (pin "2") (pinfunction "P$2_2") (pintype "passive"))
      (node (ref "C8") (pin "2") (pinfunction "P$2_2") (pintype "passive"))
      (node (ref "D1") (pin "A") (pinfunction "A_A") (pintype "passive"))
      (node (ref "D2") (pin "A") (pinfunction "A_A") (pintype "passive"))
      (node (ref "M1") (pin "P$1") (pinfunction "S_P$1") (pintype "bidirectional"))
      (node (ref "M1") (pin "P$2") (pinfunction "S_P$2") (pintype "bidirectional"))
      (node (ref "M1") (pin "P$3") (pinfunction "S_P$3") (pintype "bidirectional"))
      (node (ref "R10") (pin "1") (pinfunction "1_1") (pintype "passive"))
      (node (ref "R12") (pin "1") (pinfunction "1_1") (pintype "passive"))
      (node (ref "R19") (pin "P$1") (pinfunction "1_P$1") (pintype "passive"))
      (node (ref "R2") (pin "2") (pinfunction "2_2") (pintype "passive"))
      (node (ref "R21") (pin "1") (pinfunction "1_1") (pintype "passive"))
      (node (ref "R24") (pin "P$1") (pinfunction "1_P$1") (pintype "passive"))
      (node (ref "R25") (pin "1") (pinfunction "1_1") (pintype "passive"))
      (node (ref "R26") (pin "2") (pinfunction "2_2") (pintype "passive"))
      (node (ref "R28") (pin "1") (pinfunction "1_1") (pintype "passive"))
      (node (ref "R3") (pin "P$1") (pinfunction "1_P$1") (pintype "passive"))
      (node (ref "R30") (pin "2") (pinfunction "2_2") (pintype "passive"))
      (node (ref "R34") (pin "1") (pinfunction "1_1") (pintype "passive"))
      (node (ref "R4") (pin "1") (pinfunction "1_1") (pintype "passive"))
      (node (ref "R44") (pin "1") (pinfunction "1_1") (pintype "passive"))
      (node (ref "R46") (pin "1") (pinfunction "1_1") (pintype "passive"))
      (node (ref "R48") (pin "1") (pinfunction "1_1") (pintype "passive"))
      (node (ref "R50") (pin "1") (pinfunction "1_1") (pintype "passive"))
      (node (ref "R51") (pin "2") (pinfunction "2_2") (pintype "passive"))
      (node (ref "R56") (pin "1") (pinfunction "1_1") (pintype "passive"))
      (node (ref "R57") (pin "1") (pinfunction "1_1") (pintype "passive"))
      (node (ref "R58") (pin "1") (pinfunction "1_1") (pintype "passive"))
      (node (ref "R6") (pin "1") (pinfunction "1_1") (pintype "passive"))
      (node (ref "R77") (pin "1") (pinfunction "1_1") (pintype "passive"))
      (node (ref "SW1") (pin "P$1") (pinfunction "GND_P$1") (pintype "bidirectional"))
      (node (ref "U1") (pin "P$12") (pinfunction "NTC_P$12") (pintype "bidirectional"))
      (node (ref "U1") (pin "P$17") (pinfunction "GND_P$17") (pintype "bidirectional"))
      (node (ref "U1") (pin "P$5") (pinfunction "GND_P$5") (pintype "bidirectional"))
      (node (ref "U2") (pin "P$2") (pinfunction "GND_P$2") (pintype "bidirectional"))
      (node (ref "U3") (pin "P$1") (pinfunction "-IN_P$1") (pintype "bidirectional"))
      (node (ref "U3") (pin "P$2") (pinfunction "GND_P$2") (pintype "bidirectional"))
      (node (ref "U4") (pin "P$1") (pinfunction "S2_P$1") (pintype "bidirectional"))
      (node (ref "U5") (pin "P$12") (pinfunction "NTC_P$12") (pintype "bidirectional"))
      (node (ref "U5") (pin "P$17") (pinfunction "GND_P$17") (pintype "bidirectional"))
      (node (ref "U5") (pin "P$5") (pinfunction "GND_P$5") (pintype "bidirectional"))
      (node (ref "U6") (pin "S2") (pinfunction "S2_S2") (pintype "bidirectional"))
      (node (ref "U7") (pin "P$3") (pinfunction "S2_P$3") (pintype "bidirectional"))
      (node (ref "V10") (pin "P$1") (pinfunction "P$1_P$1") (pintype "bidirectional"))
      (node (ref "V3") (pin "P$1") (pinfunction "P$1_P$1") (pintype "bidirectional"))
      (node (ref "V4") (pin "P$1") (pinfunction "P$1_P$1") (pintype "bidirectional"))
      (node (ref "V41") (pin "P$1") (pinfunction "P$1_P$1") (pintype "bidirectional"))
      (node (ref "V5") (pin "P$1") (pinfunction "P$1_P$1") (pintype "bidirectional"))
      (node (ref "V6") (pin "P$1") (pinfunction "P$1_P$1") (pintype "bidirectional"))
      (node (ref "V7") (pin "P$1") (pinfunction "P$1_P$1") (pintype "bidirectional"))
      (node (ref "V8") (pin "P$1") (pinfunction "P$1_P$1") (pintype "bidirectional"))
    )
    (net (code "37") (name "Net-(C1-P$1)") (class "Default")
      (node (ref "C1") (pin "1") (pinfunction "P$1_1") (pintype "passive"))
      (node (ref "R1") (pin "1") (pinfunction "1_1") (pintype "passive"))
      (node (ref "U6") (pin "VDD") (pinfunction "VDD_VDD") (pintype "bidirectional"))
    )
    (net (code "38") (name "Net-(C1-P$2)") (class "Default")
      (node (ref "C1") (pin "2") (pinfunction "P$2_2") (pintype "passive"))
      (node (ref "C2") (pin "2") (pinfunction "P$2_2") (pintype "passive"))
      (node (ref "R24") (pin "P$2") (pinfunction "2_P$2") (pintype "passive"))
      (node (ref "R29") (pin "1") (pinfunction "1_1") (pintype "passive"))
      (node (ref "R3") (pin "P$2") (pinfunction "2_P$2") (pintype "passive"))
      (node (ref "R31") (pin "2") (pinfunction "2_2") (pintype "passive"))
      (node (ref "R8") (pin "P$1") (pinfunction "1_P$1") (pintype "passive"))
      (node (ref "U2") (pin "P$1") (pinfunction "-IN_P$1") (pintype "bidirectional"))
      (node (ref "U4") (pin "P$3") (pinfunction "TST_P$3") (pintype "bidirectional"))
      (node (ref "U4") (pin "P$6") (pinfunction "S1_P$6") (pintype "bidirectional"))
      (node (ref "U6") (pin "S1") (pinfunction "S1_S1") (pintype "bidirectional"))
    )
    (net (code "39") (name "Net-(C2-P$1)") (class "Default")
      (node (ref "C2") (pin "1") (pinfunction "P$1_1") (pintype "passive"))
      (node (ref "R20") (pin "1") (pinfunction "1_1") (pintype "passive"))
      (node (ref "U4") (pin "P$5") (pinfunction "VCC_P$5") (pintype "bidirectional"))
    )
    (net (code "40") (name "Net-(C23-P$1)") (class "Default")
      (node (ref "C23") (pin "1") (pinfunction "P$1_1") (pintype "passive"))
      (node (ref "M2") (pin "3") (pinfunction "S_3") (pintype "bidirectional"))
      (node (ref "SW1") (pin "P$5") (pinfunction "OUT_P$5") (pintype "power_in"))
      (node (ref "SW1") (pin "P$6") (pinfunction "OUT_P$6") (pintype "power_in"))
      (node (ref "SW1") (pin "P$7") (pinfunction "OUT_P$7") (pintype "power_in"))
      (node (ref "V21") (pin "P$1") (pinfunction "P$1_P$1") (pintype "bidirectional"))
      (node (ref "V26") (pin "P$1") (pinfunction "P$1_P$1") (pintype "bidirectional"))
    )
    (net (code "41") (name "Net-(C25-P$2)") (class "Default")
      (node (ref "C25") (pin "2") (pinfunction "P$2_2") (pintype "passive"))
      (node (ref "R77") (pin "2") (pinfunction "2_2") (pintype "passive"))
      (node (ref "R78") (pin "2") (pinfunction "2_2") (pintype "passive"))
      (node (ref "SW1") (pin "P$2") (pinfunction "CNTRL_P$2") (pintype "input"))
    )
    (net (code "42") (name "Net-(F1-P$2)") (class "Default")
      (node (ref "F1") (pin "2") (pinfunction "P$2_2") (pintype "passive"))
      (node (ref "R13") (pin "P$2") (pinfunction "2_P$2") (pintype "passive"))
      (node (ref "R22") (pin "P$2") (pinfunction "2_P$2") (pintype "passive"))
      (node (ref "V1") (pin "P$1") (pinfunction "P$1_P$1") (pintype "bidirectional"))
      (node (ref "V37") (pin "P$1") (pinfunction "P$1_P$1") (pintype "bidirectional"))
    )
    (net (code "43") (name "Net-(F5-P$2)") (class "Default")
      (node (ref "D2") (pin "C") (pinfunction "C_C") (pintype "passive"))
      (node (ref "F4") (pin "P$2") (pinfunction "P$2_P$2") (pintype "passive"))
      (node (ref "F5") (pin "2") (pinfunction "P$2_2") (pintype "passive"))
      (node (ref "M2") (pin "2") (pinfunction "D_2") (pintype "bidirectional"))
      (node (ref "R14") (pin "P$2") (pinfunction "2_P$2") (pintype "passive"))
      (node (ref "R16") (pin "P$2") (pinfunction "2_P$2") (pintype "passive"))
      (node (ref "R23") (pin "2") (pinfunction "2_2") (pintype "passive"))
      (node (ref "SW1") (pin "PAD") (pinfunction "VB_PAD") (pintype "power_in"))
      (node (ref "V2") (pin "P$1") (pinfunction "P$1_P$1") (pintype "bidirectional"))
    )
    (net (code "44") (name "Net-(M2-G)") (class "Default")
      (node (ref "M1") (pin "P$5") (pinfunction "D_P$5") (pintype "bidirectional"))
      (node (ref "M1") (pin "P$6") (pinfunction "D_P$6") (pintype "bidirectional"))
      (node (ref "M1") (pin "P$7") (pinfunction "D_P$7") (pintype "bidirectional"))
      (node (ref "M1") (pin "P$8") (pinfunction "D_P$8") (pintype "bidirectional"))
      (node (ref "M1") (pin "PAD") (pinfunction "D_PAD") (pintype "bidirectional"))
      (node (ref "M2") (pin "1") (pinfunction "G_1") (pintype "bidirectional"))
      (node (ref "R23") (pin "1") (pinfunction "1_1") (pintype "passive"))
    )
    (net (code "45") (name "Net-(R2-Pad1)") (class "Default")
      (node (ref "R2") (pin "1") (pinfunction "1_1") (pintype "passive"))
      (node (ref "U6") (pin "VM") (pinfunction "VM_VM") (pintype "bidirectional"))
    )
    (net (code "46") (name "Net-(R26-Pad1)") (class "Default")
      (node (ref "R26") (pin "1") (pinfunction "1_1") (pintype "passive"))
      (node (ref "R29") (pin "2") (pinfunction "2_2") (pintype "passive"))
      (node (ref "U6") (pin "VSS") (pinfunction "VSS_VSS") (pintype "bidirectional"))
    )
    (net (code "47") (name "Net-(R54-1)") (class "Default")
      (node (ref "R54") (pin "P$1") (pinfunction "1_P$1") (pintype "passive"))
      (node (ref "U7") (pin "P$7") (pinfunction "D1_P$7") (pintype "bidirectional"))
      (node (ref "U7") (pin "P$8") (pinfunction "D1_P$8") (pintype "bidirectional"))
    )
    (net (code "48") (name "Net-(R55-1)") (class "Default")
      (node (ref "LIFEPO1") (pin "MINUS") (pinfunction "MINUS_MINUS") (pintype "power_in"))
      (node (ref "LIFEPO2") (pin "PLUS") (pinfunction "PLUS_PLUS") (pintype "power_in"))
      (node (ref "R47") (pin "2") (pinfunction "2_2") (pintype "passive"))
      (node (ref "R55") (pin "P$1") (pinfunction "1_P$1") (pintype "passive"))
      (node (ref "U7") (pin "P$1") (pinfunction "S1_P$1") (pintype "bidirectional"))
      (node (ref "V16") (pin "P$1") (pinfunction "P$1_P$1") (pintype "bidirectional"))
    )
    (net (code "49") (name "Net-(R55-2)") (class "Default")
      (node (ref "R55") (pin "P$2") (pinfunction "2_P$2") (pintype "passive"))
      (node (ref "U7") (pin "P$5") (pinfunction "D2_P$5") (pintype "bidirectional"))
      (node (ref "U7") (pin "P$6") (pinfunction "D2_P$6") (pintype "bidirectional"))
    )
    (net (code "50") (name "Net-(SW1-ISNS)") (class "Default")
      (node (ref "R58") (pin "2") (pinfunction "2_2") (pintype "passive"))
      (node (ref "R79") (pin "2") (pinfunction "2_2") (pintype "passive"))
      (node (ref "SW1") (pin "P$3") (pinfunction "ISNS_P$3") (pintype "output"))
    )
    (net (code "51") (name "Net-(U2-OUT)") (class "Default")
      (node (ref "U2") (pin "P$5") (pinfunction "OUT_P$5") (pintype "bidirectional"))
      (node (ref "V43") (pin "P$1") (pinfunction "P$1_P$1") (pintype "bidirectional"))
    )
    (net (code "52") (name "Net-(U2-VREF1)") (class "Default")
      (node (ref "R10") (pin "2") (pinfunction "2_2") (pintype "passive"))
      (node (ref "R9") (pin "2") (pinfunction "2_2") (pintype "passive"))
      (node (ref "U2") (pin "P$3") (pinfunction "VREF2_P$3") (pintype "bidirectional"))
      (node (ref "U2") (pin "P$7") (pinfunction "VREF1_P$7") (pintype "bidirectional"))
      (node (ref "V12") (pin "P$1") (pinfunction "P$1_P$1") (pintype "bidirectional"))
    )
    (net (code "53") (name "Net-(U3-OUT)") (class "Default")
      (node (ref "U3") (pin "P$5") (pinfunction "OUT_P$5") (pintype "bidirectional"))
      (node (ref "V13") (pin "P$1") (pinfunction "P$1_P$1") (pintype "bidirectional"))
    )
    (net (code "54") (name "Net-(U3-VREF1)") (class "Default")
      (node (ref "R11") (pin "2") (pinfunction "2_2") (pintype "passive"))
      (node (ref "R12") (pin "2") (pinfunction "2_2") (pintype "passive"))
      (node (ref "U3") (pin "P$3") (pinfunction "VREF2_P$3") (pintype "bidirectional"))
      (node (ref "U3") (pin "P$7") (pinfunction "VREF1_P$7") (pintype "bidirectional"))
      (node (ref "V11") (pin "P$1") (pinfunction "P$1_P$1") (pintype "bidirectional"))
    )
    (net (code "55") (name "Net-(U4-CS)") (class "Default")
      (node (ref "R21") (pin "2") (pinfunction "2_2") (pintype "passive"))
      (node (ref "U4") (pin "P$2") (pinfunction "CS_P$2") (pintype "bidirectional"))
    )
    (net (code "56") (name "Net-(U4-VSS)") (class "Default")
      (node (ref "R30") (pin "1") (pinfunction "1_1") (pintype "passive"))
      (node (ref "R31") (pin "1") (pinfunction "1_1") (pintype "passive"))
      (node (ref "U4") (pin "P$4") (pinfunction "VSS_P$4") (pintype "bidirectional"))
    )
    (net (code "57") (name "Net-(U5-FBG)") (class "Default")
      (node (ref "R52") (pin "1") (pinfunction "1_1") (pintype "passive"))
      (node (ref "U5") (pin "P$11") (pinfunction "FBG_P$11") (pintype "bidirectional"))
    )
    (net (code "58") (name "unconnected-(U1-NC-PadP$11)") (class "Default")
      (node (ref "U1") (pin "P$11") (pinfunction "NC_P$11") (pintype "bidirectional"))
    )
    (net (code "59") (name "unconnected-(U2-NC-PadP$4)") (class "Default")
      (node (ref "U2") (pin "P$4") (pinfunction "NC_P$4") (pintype "bidirectional"))
    )
    (net (code "60") (name "unconnected-(U3-NC-PadP$4)") (class "Default")
      (node (ref "U3") (pin "P$4") (pinfunction "NC_P$4") (pintype "bidirectional"))
    )
    (net (code "61") (name "unconnected-(U6-PadNC)") (class "Default")
      (node (ref "U6") (pin "NC") (pinfunction "NC_NC") (pintype "bidirectional"))
    )
  )
)
